# LCD_Schematic.net
KiCad netlist of a schematic drawn in Altium Designer
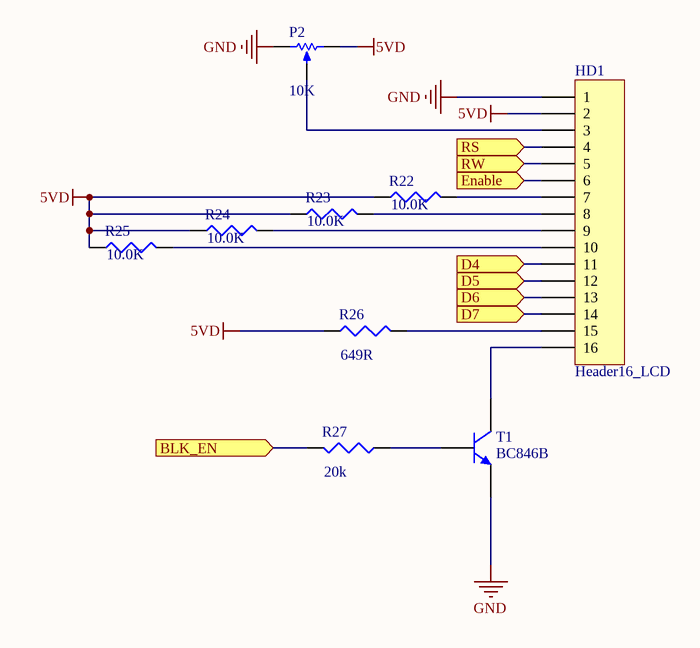
[diagram p0: LCD_Schematic.SchDoc]

(export (version "E")
  (design (tool "Eeschema 10.0.6"))
  (components
    (comp (ref "HD1")
      (value "Header16_LCD")
      (footprint "HDR1X16_LCD")
      (description "Header, 16-Pin Female")
      (libsource (lib "esd_library") (part "Header16_LCD"))
    )
    (comp (ref "P2")
      (value "10K")
      (footprint "BOURNS_3386F")
      (description "Potentiometer")
      (fields (field (name "Comment") "RPot") (field (name "PUBLISHER") "Altium Limited"))
      (libsource (lib "esd_library") (part "RPot"))
    )
    (comp (ref "R22")
      (value "10.0K")
      (footprint "RESC2112X05M")
      (description "RES SMD 10.0K OHM 1% 1/8W 0805")
      (fields (field (name "MPN") "CRCW080510K0FKEA") (field (name "Comment") "Res3"))
      (libsource (lib "esd_library") (part "Resistor_10.0K"))
    )
    (comp (ref "R23")
      (value "10.0K")
      (footprint "RESC2112X05M")
      (description "RES SMD 10.0K OHM 1% 1/8W 0805")
      (fields (field (name "MPN") "CRCW080510K0FKEA") (field (name "Comment") "Res3"))
      (libsource (lib "esd_library") (part "Resistor_10.0K"))
    )
    (comp (ref "R24")
      (value "10.0K")
      (footprint "RESC2112X05M")
      (description "RES SMD 10.0K OHM 1% 1/8W 0805")
      (fields (field (name "MPN") "CRCW080510K0FKEA") (field (name "Comment") "Res3"))
      (libsource (lib "esd_library") (part "Resistor_10.0K"))
    )
    (comp (ref "R25")
      (value "10.0K")
      (footprint "RESC2112X05M")
      (description "RES SMD 10.0K OHM 1% 1/8W 0805")
      (fields (field (name "MPN") "CRCW080510K0FKEA") (field (name "Comment") "Res3"))
      (libsource (lib "esd_library") (part "Resistor_10.0K"))
    )
    (comp (ref "R26")
      (value "649R")
      (footprint "RESC2112X05M")
      (description "RES SMD 649R OHM 1% 1/8W 0805")
      (fields (field (name "MPN") "CRCW0805649RFKEA") (field (name "Comment") "Res3"))
      (libsource (lib "esd_library") (part "Resistor_649R"))
    )
    (comp (ref "R27")
      (value "20k")
      (footprint "RESC2112X05M")
      (description "RES SMD 1.00K OHM 1% 1/8W 0805")
      (fields (field (name "MPN") "CRCW08051K00FKEA") (field (name "Comment") "Res3"))
      (libsource (lib "esd_library") (part "Resistor_1.00K"))
    )
    (comp (ref "T1")
      (value "BC846B")
      (footprint "SOT95P230X110-3M")
      (description "NPN General Purpose Amplifier")
      (libsource (lib "esd_library") (part "BC846B"))
    )
  )
  (nets
    (net (code "1") (name "/BLK_EN") (class "Default")
      (node (ref "R27") (pin "2") (pinfunction "2_2") (pintype "passive"))
    )
    (net (code "2") (name "/D4") (class "Default")
      (node (ref "HD1") (pin "11") (pinfunction "11_11") (pintype "passive"))
    )
    (net (code "3") (name "/D5") (class "Default")
      (node (ref "HD1") (pin "12") (pinfunction "12_12") (pintype "passive"))
    )
    (net (code "4") (name "/D6") (class "Default")
      (node (ref "HD1") (pin "13") (pinfunction "13_13") (pintype "passive"))
    )
    (net (code "5") (name "/D7") (class "Default")
      (node (ref "HD1") (pin "14") (pinfunction "14_14") (pintype "passive"))
    )
    (net (code "6") (name "/Enable") (class "Default")
      (node (ref "HD1") (pin "6") (pinfunction "6_6") (pintype "passive"))
    )
    (net (code "7") (name "/RS") (class "Default")
      (node (ref "HD1") (pin "4") (pinfunction "4_4") (pintype "passive"))
    )
    (net (code "8") (name "/RW") (class "Default")
      (node (ref "HD1") (pin "5") (pinfunction "5_5") (pintype "passive"))
    )
    (net (code "9") (name "5VD") (class "Default")
      (node (ref "HD1") (pin "2") (pinfunction "2_2") (pintype "passive"))
      (node (ref "P2") (pin "3") (pinfunction "BOT_3") (pintype "passive"))
      (node (ref "R22") (pin "1") (pinfunction "1_1") (pintype "passive"))
      (node (ref "R23") (pin "1") (pinfunction "1_1") (pintype "passive"))
      (node (ref "R24") (pin "1") (pinfunction "1_1") (pintype "passive"))
      (node (ref "R25") (pin "1") (pinfunction "1_1") (pintype "passive"))
      (node (ref "R26") (pin "1") (pinfunction "1_1") (pintype "passive"))
    )
    (net (code "10") (name "GND") (class "Default")
      (node (ref "HD1") (pin "1") (pinfunction "1_1") (pintype "passive"))
      (node (ref "P2") (pin "1") (pinfunction "TOP_1") (pintype "passive"))
      (node (ref "T1") (pin "2") (pinfunction "E_2") (pintype "passive"))
    )
    (net (code "11") (name "Net-(HD1-Pad7)") (class "Default")
      (node (ref "HD1") (pin "7") (pinfunction "7_7") (pintype "passive"))
      (node (ref "R22") (pin "2") (pinfunction "2_2") (pintype "passive"))
    )
    (net (code "12") (name "Net-(HD1-Pad8)") (class "Default")
      (node (ref "HD1") (pin "8") (pinfunction "8_8") (pintype "passive"))
      (node (ref "R23") (pin "2") (pinfunction "2_2") (pintype "passive"))
    )
    (net (code "13") (name "Net-(HD1-Pad9)") (class "Default")
      (node (ref "HD1") (pin "9") (pinfunction "9_9") (pintype "passive"))
      (node (ref "R24") (pin "2") (pinfunction "2_2") (pintype "passive"))
    )
    (net (code "14") (name "Net-(HD1-Pad10)") (class "Default")
      (node (ref "HD1") (pin "10") (pinfunction "10_10") (pintype "passive"))
      (node (ref "R25") (pin "2") (pinfunction "2_2") (pintype "passive"))
    )
    (net (code "15") (name "Net-(HD1-Pad15)") (class "Default")
      (node (ref "HD1") (pin "15") (pinfunction "15_15") (pintype "passive"))
      (node (ref "R26") (pin "2") (pinfunction "2_2") (pintype "passive"))
    )
    (net (code "16") (name "Net-(P2-TAP)") (class "Default")
      (node (ref "HD1") (pin "3") (pinfunction "3_3") (pintype "passive"))
      (node (ref "P2") (pin "2") (pinfunction "TAP_2") (pintype "passive"))
    )
    (net (code "17") (name "Net-(T1-B)") (class "Default")
      (node (ref "R27") (pin "1") (pinfunction "1_1") (pintype "passive"))
      (node (ref "T1") (pin "1") (pinfunction "B_1") (pintype "passive"))
    )
    (net (code "18") (name "Net-(T1-C)") (class "Default")
      (node (ref "HD1") (pin "16") (pinfunction "16_16") (pintype "passive"))
      (node (ref "T1") (pin "3") (pinfunction "C_3") (pintype "passive"))
    )
  )
)
